# POWER_GATEWAY.net
KiCad netlist of a schematic drawn in Altium Designer
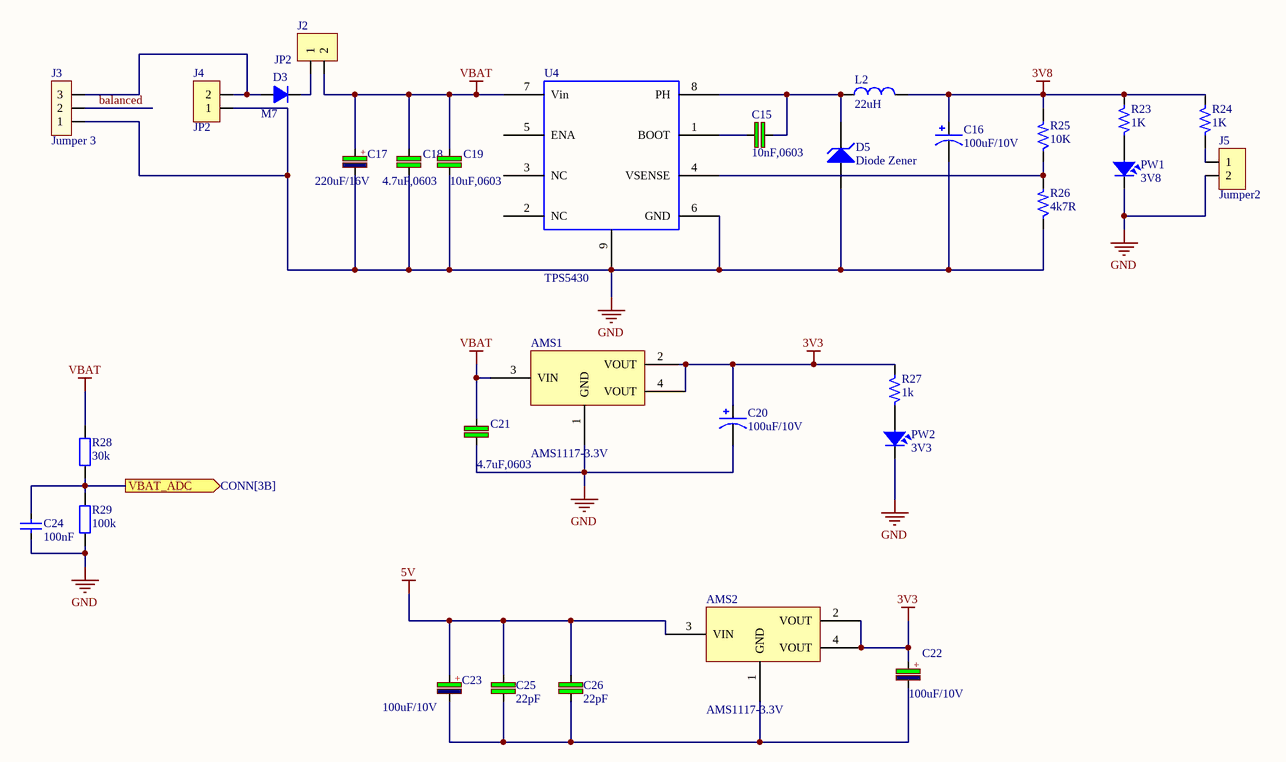
[diagram p0: POWER_GATEWAY.SchDoc]

(export (version "E")
  (design (tool "Eeschema 10.0.6"))
  (components
    (comp (ref "AMS1")
      (value "AMS1117-3.3V")
      (footprint "SOT223")
      (description "Dán")
      (libsource (lib "IC") (part "AMS1117 SMD"))
    )
    (comp (ref "AMS2")
      (value "AMS1117-3.3V")
      (footprint "SOT223")
      (description "Dán")
      (libsource (lib "IC") (part "AMS1117 SMD"))
    )
    (comp (ref "C15")
      (value "10nF,0603")
      (footprint "CAP_0603")
      (description "4.7µF ±10% 35V Ceramic Capacitor X5R 0805 (2012 Metric)")
      (fields
        (field (name "MANUFACTURER") "Samsung Electro-Mechanics")
        (field (name "PART NUMBER") "CL21A475KLCLQNC")
      )
      (libsource (lib "") (part "C_1"))
    )
    (comp (ref "C16")
      (value "100uF/10V")
      (footprint "CAP-ALU-SMD-C")
      (description "Polarized Capacitor (Axial)")
      (fields (field (name "PUBLISHER") "Altium Limited"))
      (libsource (lib "My Library") (part "Cap Pol"))
    )
    (comp (ref "C17")
      (value "220uF/16V")
      (footprint "CAP-ALU-SMD-D")
      (description "Cap 470uF/63V")
      (libsource (lib "Main") (part "CP3"))
    )
    (comp (ref "C18")
      (value "4.7uF,0603")
      (footprint "CAP_0603")
      (description "4.7µF ±10% 35V Ceramic Capacitor X5R 0805 (2012 Metric)")
      (fields
        (field (name "MANUFACTURER") "Samsung Electro-Mechanics")
        (field (name "PART NUMBER") "CL21A475KLCLQNC")
      )
      (libsource (lib "Anh_Trung") (part "C"))
    )
    (comp (ref "C19")
      (value "10uF,0603")
      (footprint "CAP_0603")
      (description "4.7µF ±10% 35V Ceramic Capacitor X5R 0805 (2012 Metric)")
      (fields
        (field (name "MANUFACTURER") "Samsung Electro-Mechanics")
        (field (name "PART NUMBER") "CL21A475KLCLQNC")
      )
      (libsource (lib "Anh_Trung") (part "C"))
    )
    (comp (ref "C20")
      (value "100uF/10V")
      (footprint "CAP-ALU-SMD-C")
      (description "Polarized Capacitor (Axial)")
      (fields (field (name "PUBLISHER") "Altium Limited"))
      (libsource (lib "My Library") (part "Cap Pol"))
    )
    (comp (ref "C21")
      (value "4.7uF,0603")
      (footprint "CAP_0603")
      (description "4.7µF ±10% 35V Ceramic Capacitor X5R 0805 (2012 Metric)")
      (fields
        (field (name "MANUFACTURER") "Samsung Electro-Mechanics")
        (field (name "PART NUMBER") "CL21A475KLCLQNC")
      )
      (libsource (lib "Anh_Trung") (part "C"))
    )
    (comp (ref "C22")
      (value "100uF/10V")
      (footprint "CAP-ALU-SMD-C")
      (description "Cap 470uF/63V")
      (libsource (lib "Main") (part "CP3"))
    )
    (comp (ref "C23")
      (value "100uF/10V")
      (footprint "CAP-ALU-SMD-C")
      (description "Cap 470uF/63V")
      (libsource (lib "Main") (part "CP3"))
    )
    (comp (ref "C24")
      (value "100nF")
      (footprint "CAP_0805")
      (description "Capacitor")
      (fields (field (name "PUBLISHER") "Altium Limited"))
      (libsource (lib "My Library") (part "CapSMD"))
    )
    (comp (ref "C25")
      (value "22pF")
      (footprint "CAP_0603")
      (description "Cap SMD")
      (fields
        (field (name "MANUFACTURER") "Samsung Electro-Mechanics")
        (field (name "PART NUMBER") "CL21A106KPFNNNG")
      )
      (libsource (lib "") (part "C_1"))
    )
    (comp (ref "C26")
      (value "22pF")
      (footprint "CAP_0603")
      (description "Cap SMD")
      (fields
        (field (name "MANUFACTURER") "Samsung Electro-Mechanics")
        (field (name "PART NUMBER") "CL21A106KPFNNNG")
      )
      (libsource (lib "") (part "C_1"))
    )
    (comp (ref "D3")
      (value "M7")
      (footprint "SMA")
      (description "Diode 1A")
      (libsource (lib "Main") (part "D1A"))
    )
    (comp (ref "D5")
      (value "Diode Zener")
      (footprint "SMA")
      (description "Zener Diode")
      (fields (field (name "PUBLISHER") "Altium Limited"))
      (libsource (lib "My Library 2") (part "Diode Zener"))
    )
    (comp (ref "J2")
      (value "JP2")
      (footprint "KF2-5.08")
      (description "WR-PHD 2.54 mm Angled Socket Header")
      (fields
        (field (name "MANUFACTURER") "Würth Elektronik eiSos GmbH")
        (field (name "PARTNO") "613002143121")
        (field (name "CREATED BY") "Karrer Zheng")
      )
      (libsource (lib "My Library") (part "JP2"))
    )
    (comp (ref "J3") (value "Jumper 3") (footprint "KF3-5.08") (libsource (lib "My Library") (part "JP3")))
    (comp (ref "J4")
      (value "JP2")
      (footprint "KF2-5.08")
      (description "WR-PHD 2.54 mm Angled Socket Header")
      (fields
        (field (name "MANUFACTURER") "Würth Elektronik eiSos GmbH")
        (field (name "PARTNO") "613002143121")
        (field (name "CREATED BY") "Karrer Zheng")
      )
      (libsource (lib "") (part "JP2_1"))
    )
    (comp (ref "J5")
      (value "Jumper2")
      (footprint "CON2")
      (description "WR-PHD 2.54 mm Angled Socket Header")
      (fields
        (field (name "MANUFACTURER") "Würth Elektronik eiSos GmbH")
        (field (name "PARTNO") "613002143121")
        (field (name "CREATED BY") "Karrer Zheng")
      )
      (libsource (lib "") (part "JP2_2"))
    )
    (comp (ref "L2")
      (value "22uH")
      (footprint "L-SMD-M-7.3x4.5")
      (description "22µH Shielded Inductor 1.65A 96mOhm Max Nonstandard")
      (fields (field (name "MANUFACTURER") "Bourns Inc.") (field (name "PART NUMBER") "SRR0745A-220M"))
      (libsource (lib "Main") (part "L1"))
    )
    (comp (ref "PW1")
      (value "3V8")
      (footprint "LED-0805-Blue")
      (description "LED RED DIFFUSED 0805 SMD")
      (fields
        (field (name "MANUFACTURER") "OSRAM Opto Semiconductors Inc.")
        (field (name "PART NUMBER") "LS R976-NR-1")
      )
      (libsource (lib "Anh_Trung") (part "LED"))
    )
    (comp (ref "PW2")
      (value "3V3")
      (footprint "LED-0805-Blue")
      (description "LED RED DIFFUSED 0805 SMD")
      (fields
        (field (name "MANUFACTURER") "OSRAM Opto Semiconductors Inc.")
        (field (name "PART NUMBER") "LS R976-NR-1")
      )
      (libsource (lib "Anh_Trung") (part "LED"))
    )
    (comp (ref "R23")
      (value "1K")
      (footprint "RES-SMD-0805")
      (description "Resistor 1/4W")
      (fields (field (name "MANUFACTURER") "Yageo") (field (name "PART NUMBER") "RC0805FR-071KL"))
      (libsource (lib "Anh_Trung") (part "R"))
    )
    (comp (ref "R24")
      (value "1K")
      (footprint "RES-SMD-0805")
      (description "Resistor 1/4W")
      (fields (field (name "MANUFACTURER") "Yageo") (field (name "PART NUMBER") "RC0805FR-071KL"))
      (libsource (lib "Anh_Trung") (part "R"))
    )
    (comp (ref "R25")
      (value "10K")
      (footprint "RES-SMD-0603")
      (description "RES SMD 10K OHM 1% 1/8W 0805")
      (fields (field (name "MANUFACTURER") "Yageo") (field (name "PART NUMBER") "RC0805FR-0710KL"))
      (libsource (lib "Anh_Trung") (part "R"))
    )
    (comp (ref "R26")
      (value "4k7R")
      (footprint "RES-SMD-0603")
      (description "RES SMD 3.3K OHM 1% 1/8W 0805")
      (fields (field (name "MANUFACTURER") "Yageo") (field (name "PART NUMBER") "RC0805FR-073K3L"))
      (libsource (lib "Anh_Trung") (part "R"))
    )
    (comp (ref "R27")
      (value "1k")
      (footprint "RES-SMD-0603")
      (description "Resistor 1/4W")
      (fields (field (name "MANUFACTURER") "Yageo") (field (name "PART NUMBER") "RC0805FR-071KL"))
      (libsource (lib "Anh_Trung") (part "R"))
    )
    (comp (ref "R28")
      (value "30k")
      (footprint "RES-SMD-0805")
      (description "Resistor SMD")
      (fields
        (field (name "MANUFACTURER") "Generic Components")
        (field (name "PUBLISHER") "Altium Hobart Technology Centre")
      )
      (libsource (lib "My Library") (part "Resistor - SMD"))
    )
    (comp (ref "R29")
      (value "100k")
      (footprint "RES-SMD-0805")
      (description "Resistor SMD")
      (fields
        (field (name "MANUFACTURER") "Generic Components")
        (field (name "PUBLISHER") "Altium Hobart Technology Centre")
      )
      (libsource (lib "My Library") (part "Resistor - SMD"))
    )
    (comp (ref "U4")
      (value "TPS5430")
      (footprint "TPS5430-2")
      (fields (field (name "NAME") "TPS5430"))
      (libsource (lib "My Library 2") (part "TPS5430"))
    )
  )
  (nets
    (net (code "1") (name "/VBAT_ADC") (class "Default")
      (node (ref "C24") (pin "2") (pinfunction "2_2") (pintype "passive"))
      (node (ref "R28") (pin "1") (pinfunction "1_1") (pintype "passive"))
      (node (ref "R29") (pin "2") (pinfunction "2_2") (pintype "passive"))
    )
    (net (code "2") (name "/balanced") (class "Default")
      (node (ref "J3") (pin "2") (pinfunction "2_2") (pintype "passive"))
    )
    (net (code "3") (name "3V3") (class "Default")
      (node (ref "AMS1") (pin "2") (pinfunction "VOUT_2") (pintype "passive"))
      (node (ref "AMS1") (pin "4") (pinfunction "VOUT_4") (pintype "passive"))
      (node (ref "AMS2") (pin "2") (pinfunction "VOUT_2") (pintype "passive"))
      (node (ref "AMS2") (pin "4") (pinfunction "VOUT_4") (pintype "passive"))
      (node (ref "C20") (pin "1") (pinfunction "1_1") (pintype "passive"))
      (node (ref "C22") (pin "1") (pinfunction "1_1") (pintype "passive"))
      (node (ref "R27") (pin "1") (pinfunction "1_1") (pintype "passive"))
    )
    (net (code "4") (name "3V8") (class "Default")
      (node (ref "C16") (pin "1") (pinfunction "1_1") (pintype "passive"))
      (node (ref "L2") (pin "2") (pinfunction "2_2") (pintype "passive"))
      (node (ref "R23") (pin "1") (pinfunction "1_1") (pintype "passive"))
      (node (ref "R24") (pin "1") (pinfunction "1_1") (pintype "passive"))
      (node (ref "R25") (pin "2") (pinfunction "2_2") (pintype "passive"))
    )
    (net (code "5") (name "5V") (class "Default")
      (node (ref "AMS2") (pin "3") (pinfunction "VIN_3") (pintype "passive"))
      (node (ref "C23") (pin "1") (pinfunction "1_1") (pintype "passive"))
      (node (ref "C25") (pin "1") (pinfunction "1_1") (pintype "passive"))
      (node (ref "C26") (pin "1") (pinfunction "1_1") (pintype "passive"))
    )
    (net (code "6") (name "GND") (class "Default")
      (node (ref "AMS1") (pin "1") (pinfunction "GND_1") (pintype "passive"))
      (node (ref "C16") (pin "2") (pinfunction "2_2") (pintype "passive"))
      (node (ref "C17") (pin "2") (pinfunction "2_2") (pintype "passive"))
      (node (ref "C18") (pin "1") (pinfunction "1_1") (pintype "passive"))
      (node (ref "C19") (pin "1") (pinfunction "1_1") (pintype "passive"))
      (node (ref "C20") (pin "2") (pinfunction "2_2") (pintype "passive"))
      (node (ref "C21") (pin "1") (pinfunction "1_1") (pintype "passive"))
      (node (ref "C24") (pin "1") (pinfunction "1_1") (pintype "passive"))
      (node (ref "D5") (pin "1") (pinfunction "A_1") (pintype "passive"))
      (node (ref "J3") (pin "1") (pinfunction "1_1") (pintype "passive"))
      (node (ref "J4") (pin "1") (pinfunction "1_1") (pintype "passive"))
      (node (ref "J5") (pin "2") (pinfunction "2_2") (pintype "passive"))
      (node (ref "PW1") (pin "2") (pinfunction "2_2") (pintype "passive"))
      (node (ref "PW2") (pin "2") (pinfunction "2_2") (pintype "passive"))
      (node (ref "R26") (pin "1") (pinfunction "1_1") (pintype "passive"))
      (node (ref "R29") (pin "1") (pinfunction "1_1") (pintype "passive"))
      (node (ref "U4") (pin "6") (pinfunction "GND_6") (pintype "passive"))
      (node (ref "U4") (pin "9") (pinfunction "PWR_PAD_9") (pintype "passive"))
    )
    (net (code "7") (name "Net-(AMS2-GND)") (class "Default")
      (node (ref "AMS2") (pin "1") (pinfunction "GND_1") (pintype "passive"))
      (node (ref "C22") (pin "2") (pinfunction "2_2") (pintype "passive"))
      (node (ref "C23") (pin "2") (pinfunction "2_2") (pintype "passive"))
      (node (ref "C25") (pin "2") (pinfunction "2_2") (pintype "passive"))
      (node (ref "C26") (pin "2") (pinfunction "2_2") (pintype "passive"))
    )
    (net (code "8") (name "Net-(D3-A)") (class "Default")
      (node (ref "D3") (pin "1") (pinfunction "A_1") (pintype "passive"))
      (node (ref "J3") (pin "3") (pinfunction "3_3") (pintype "passive"))
      (node (ref "J4") (pin "2") (pinfunction "2_2") (pintype "passive"))
    )
    (net (code "9") (name "Net-(D3-K)") (class "Default")
      (node (ref "D3") (pin "2") (pinfunction "K_2") (pintype "passive"))
      (node (ref "J2") (pin "1") (pinfunction "1_1") (pintype "passive"))
    )
    (net (code "10") (name "Net-(D5-K)") (class "Default")
      (node (ref "C15") (pin "1") (pinfunction "1_1") (pintype "passive"))
      (node (ref "D5") (pin "2") (pinfunction "K_2") (pintype "passive"))
      (node (ref "L2") (pin "1") (pinfunction "1_1") (pintype "passive"))
      (node (ref "U4") (pin "8") (pinfunction "PH_8") (pintype "passive"))
    )
    (net (code "11") (name "Net-(J5-Pad1)") (class "Default")
      (node (ref "J5") (pin "1") (pinfunction "1_1") (pintype "passive"))
      (node (ref "R24") (pin "2") (pinfunction "2_2") (pintype "passive"))
    )
    (net (code "12") (name "Net-(PW1-Pad1)") (class "Default")
      (node (ref "PW1") (pin "1") (pinfunction "1_1") (pintype "passive"))
      (node (ref "R23") (pin "2") (pinfunction "2_2") (pintype "passive"))
    )
    (net (code "13") (name "Net-(PW2-Pad1)") (class "Default")
      (node (ref "PW2") (pin "1") (pinfunction "1_1") (pintype "passive"))
      (node (ref "R27") (pin "2") (pinfunction "2_2") (pintype "passive"))
    )
    (net (code "14") (name "Net-(U4-BOOT)") (class "Default")
      (node (ref "C15") (pin "2") (pinfunction "2_2") (pintype "passive"))
      (node (ref "U4") (pin "1") (pinfunction "BOOT_1") (pintype "passive"))
    )
    (net (code "15") (name "Net-(U4-VSENSE)") (class "Default")
      (node (ref "R25") (pin "1") (pinfunction "1_1") (pintype "passive"))
      (node (ref "R26") (pin "2") (pinfunction "2_2") (pintype "passive"))
      (node (ref "U4") (pin "4") (pinfunction "VSENSE_4") (pintype "passive"))
    )
    (net (code "16") (name "VBAT") (class "Default")
      (node (ref "AMS1") (pin "3") (pinfunction "VIN_3") (pintype "passive"))
      (node (ref "C17") (pin "1") (pinfunction "1_1") (pintype "passive"))
      (node (ref "C18") (pin "2") (pinfunction "2_2") (pintype "passive"))
      (node (ref "C19") (pin "2") (pinfunction "2_2") (pintype "passive"))
      (node (ref "C21") (pin "2") (pinfunction "2_2") (pintype "passive"))
      (node (ref "J2") (pin "2") (pinfunction "2_2") (pintype "passive"))
      (node (ref "R28") (pin "2") (pinfunction "2_2") (pintype "passive"))
      (node (ref "U4") (pin "7") (pinfunction "Vin_7") (pintype "passive"))
    )
    (net (code "17") (name "unconnected-(U4-ENA-Pad5)") (class "Default")
      (node (ref "U4") (pin "5") (pinfunction "ENA_5") (pintype "passive"))
    )
    (net (code "18") (name "unconnected-(U4-NC-Pad2)") (class "Default")
      (node (ref "U4") (pin "2") (pinfunction "NC_2") (pintype "passive"))
    )
    (net (code "19") (name "unconnected-(U4-NC-Pad3)") (class "Default")
      (node (ref "U4") (pin "3") (pinfunction "NC_3") (pintype "passive"))
    )
  )
)
